# Audio_Amplifier_bass_boost.net
KiCad netlist of a schematic drawn in EAGLE
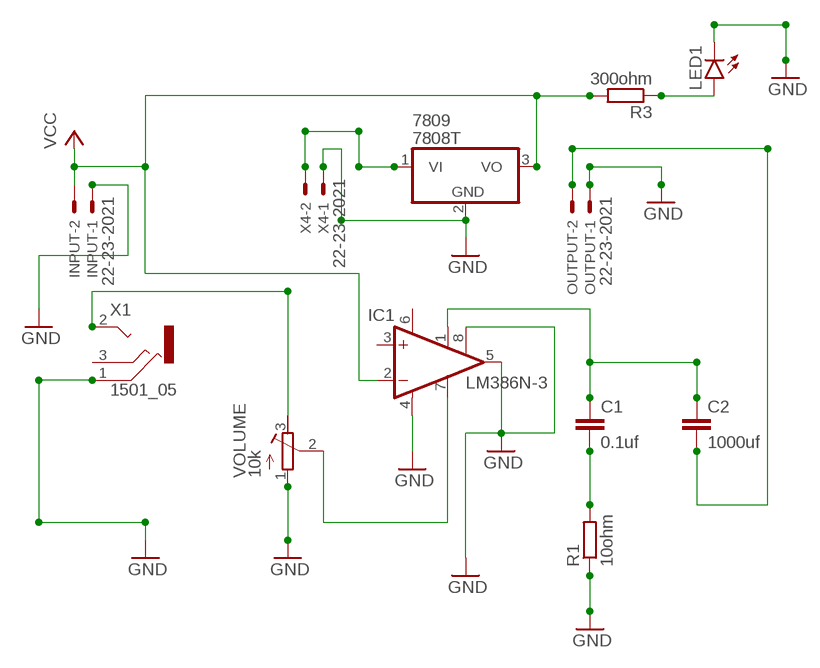
[diagram p0: schematic, sheet 1]

(export (version "E")
  (design (tool "Eeschema 10.0.6"))
  (components
    (comp (ref "7809")
      (value "7808T")
      (footprint "eagle-import:TO220H")
      (libsource (lib "eagle-import") (part "78T08"))
    )
    (comp (ref "C1")
      (value "0.1uf")
      (footprint "eagle-import:C2.5-2")
      (libsource (lib "eagle-import") (part "C2.5/2"))
    )
    (comp (ref "C2")
      (value "1000uf")
      (footprint "eagle-import:C5B3")
      (libsource (lib "eagle-import") (part "C5/3"))
    )
    (comp (ref "IC1")
      (value "LM386N-3")
      (footprint "eagle-import:DIL08")
      (libsource (lib "eagle-import") (part "LM386?-N3"))
    )
    (comp (ref "INPUT")
      (value "22-23-2021")
      (footprint "eagle-import:22-23-2021")
      (fields (field (name "MF") "MOLEX"))
      (libsource (lib "eagle-import") (part "22-23-2021"))
    )
    (comp (ref "LED1")
      (value "LED5MM")
      (footprint "eagle-import:LED5MM")
      (libsource (lib "eagle-import") (part "LED5MM"))
    )
    (comp (ref "OUTPUT")
      (value "22-23-2021")
      (footprint "eagle-import:22-23-2021")
      (fields (field (name "MF") "MOLEX"))
      (libsource (lib "eagle-import") (part "22-23-2021"))
    )
    (comp (ref "R1")
      (value "10ohm")
      (footprint "eagle-import:0207_7")
      (libsource (lib "eagle-import") (part "R-EU_0207/7"))
    )
    (comp (ref "R3")
      (value "300ohm")
      (footprint "eagle-import:0207_7")
      (libsource (lib "eagle-import") (part "R-EU_0207/7"))
    )
    (comp (ref "VOLUME")
      (value "10k")
      (footprint "eagle-import:RTRIM64W")
      (libsource (lib "eagle-import") (part "R-TRIMM64W"))
    )
    (comp (ref "X1")
      (value "1501_05")
      (footprint "eagle-import:1501_05")
      (libsource (lib "eagle-import") (part "1501_05"))
    )
    (comp (ref "X4")
      (value "22-23-2021")
      (footprint "eagle-import:22-23-2021")
      (fields (field (name "MF") "MOLEX"))
      (libsource (lib "eagle-import") (part "22-23-2021"))
    )
  )
  (nets
    (net (code "1") (name "/VS") (class "Default")
      (node (ref "IC1") (pin "6") (pinfunction "VS_6") (pintype "power_in"))
    )
    (net (code "2") (name "GND") (class "Default")
      (node (ref "7809") (pin "2") (pinfunction "GND_2") (pintype "passive"))
      (node (ref "IC1") (pin "4") (pinfunction "GND_4") (pintype "power_in"))
      (node (ref "IC1") (pin "5") (pinfunction "OUT_5") (pintype "output"))
      (node (ref "IC1") (pin "8") (pinfunction "GAIN_8") (pintype "passive"))
      (node (ref "INPUT") (pin "1") (pinfunction "S_1") (pintype "passive"))
      (node (ref "LED1") (pin "K") (pinfunction "C_K") (pintype "passive"))
      (node (ref "OUTPUT") (pin "1") (pinfunction "S_1") (pintype "passive"))
      (node (ref "R1") (pin "1") (pinfunction "1_1") (pintype "passive"))
      (node (ref "VOLUME") (pin "1") (pinfunction "A_1") (pintype "passive"))
      (node (ref "X1") (pin "1") (pinfunction "1_1") (pintype "passive"))
      (node (ref "X4") (pin "1") (pinfunction "S_1") (pintype "passive"))
    )
    (net (code "3") (name "Net-(7809-VI)") (class "Default")
      (node (ref "7809") (pin "1") (pinfunction "VI_1") (pintype "input"))
      (node (ref "X4") (pin "2") (pinfunction "S_2") (pintype "passive"))
    )
    (net (code "4") (name "Net-(C1-Pad1)") (class "Default")
      (node (ref "C1") (pin "1") (pinfunction "1_1") (pintype "passive"))
      (node (ref "C2") (pin "1") (pinfunction "1_1") (pintype "passive"))
      (node (ref "IC1") (pin "1") (pinfunction "GAIN_1") (pintype "passive"))
    )
    (net (code "5") (name "Net-(C1-Pad2)") (class "Default")
      (node (ref "C1") (pin "2") (pinfunction "2_2") (pintype "passive"))
      (node (ref "R1") (pin "2") (pinfunction "2_2") (pintype "passive"))
    )
    (net (code "6") (name "Net-(IC1-BYPASS)") (class "Default")
      (node (ref "IC1") (pin "7") (pinfunction "BYPASS_7") (pintype "passive"))
      (node (ref "VOLUME") (pin "2") (pinfunction "S_2") (pintype "passive"))
    )
    (net (code "7") (name "Net-(LED1-PadA)") (class "Default")
      (node (ref "LED1") (pin "A") (pinfunction "A_A") (pintype "passive"))
      (node (ref "R3") (pin "1") (pinfunction "1_1") (pintype "passive"))
    )
    (net (code "8") (name "Net-(OUTPUTB-S)") (class "Default")
      (node (ref "C2") (pin "2") (pinfunction "2_2") (pintype "passive"))
      (node (ref "OUTPUT") (pin "2") (pinfunction "S_2") (pintype "passive"))
    )
    (net (code "9") (name "Net-(VOLUME-E)") (class "Default")
      (node (ref "VOLUME") (pin "3") (pinfunction "E_3") (pintype "passive"))
      (node (ref "X1") (pin "2") (pinfunction "2_2") (pintype "passive"))
    )
    (net (code "10") (name "VCC") (class "Default")
      (node (ref "7809") (pin "3") (pinfunction "VO_3") (pintype "passive"))
      (node (ref "IC1") (pin "2") (pinfunction "-IN_2") (pintype "input"))
      (node (ref "INPUT") (pin "2") (pinfunction "S_2") (pintype "passive"))
      (node (ref "R3") (pin "2") (pinfunction "2_2") (pintype "passive"))
    )
    (net (code "11") (name "unconnected-(IC1-+IN-Pad3)") (class "Default")
      (node (ref "IC1") (pin "3") (pinfunction "+IN_3") (pintype "input"))
    )
    (net (code "12") (name "unconnected-(X1-Pad3)") (class "Default")
      (node (ref "X1") (pin "3") (pinfunction "3_3") (pintype "passive"))
    )
  )
)
